# transformerless_power_Supply_5v.net
KiCad netlist of a schematic drawn in EAGLE
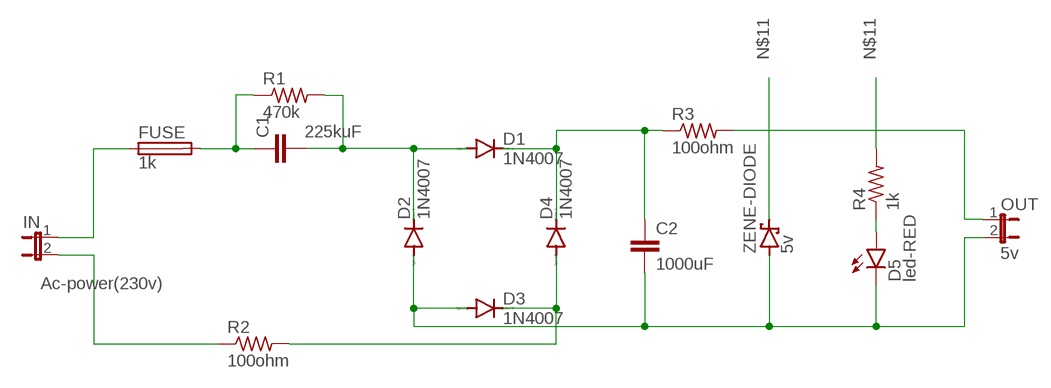
[diagram p0: schematic, sheet 1]

(export (version "E")
  (design (tool "Eeschema 10.0.6"))
  (components
    (comp (ref "C1")
      (value "225kuF")
      (footprint "eagle-import:C5B3")
      (libsource (lib "eagle-import") (part "C5/3"))
    )
    (comp (ref "C2")
      (value "1000uF")
      (footprint "eagle-import:C5B3")
      (libsource (lib "eagle-import") (part "C5/3"))
    )
    (comp (ref "D1")
      (value "1N4007")
      (footprint "eagle-import:DO41-10")
      (libsource (lib "eagle-import") (part "1N4004"))
    )
    (comp (ref "D2")
      (value "1N4007")
      (footprint "eagle-import:DO41-10")
      (libsource (lib "eagle-import") (part "1N4004"))
    )
    (comp (ref "D3")
      (value "1N4007")
      (footprint "eagle-import:DO41-10")
      (libsource (lib "eagle-import") (part "1N4004"))
    )
    (comp (ref "D4")
      (value "1N4007")
      (footprint "eagle-import:DO41-10")
      (libsource (lib "eagle-import") (part "1N4004"))
    )
    (comp (ref "D5")
      (value "led-RED")
      (footprint "eagle-import:SFH482")
      (libsource (lib "eagle-import") (part "SFH482"))
    )
    (comp (ref "FUSE")
      (value "1k")
      (footprint "eagle-import:PICOFUSE")
      (libsource (lib "eagle-import") (part "FUSEPICOFUSE"))
    )
    (comp (ref "IN")
      (value "Ac-power(230v)")
      (footprint "eagle-import:JP1")
      (libsource (lib "eagle-import") (part "JP1E"))
    )
    (comp (ref "OUT")
      (value "5v")
      (footprint "eagle-import:JP1")
      (libsource (lib "eagle-import") (part "JP1E"))
    )
    (comp (ref "R1")
      (value "470k")
      (footprint "eagle-import:0207_10")
      (libsource (lib "eagle-import") (part "R-US_0207/10"))
    )
    (comp (ref "R2")
      (value "100ohm")
      (footprint "eagle-import:0207_10")
      (libsource (lib "eagle-import") (part "R-US_0207/10"))
    )
    (comp (ref "R3")
      (value "100ohm")
      (footprint "eagle-import:0207_10")
      (libsource (lib "eagle-import") (part "R-US_0207/10"))
    )
    (comp (ref "R4")
      (value "1k")
      (footprint "eagle-import:0207_10")
      (libsource (lib "eagle-import") (part "R-US_0207/10"))
    )
    (comp (ref "ZENE-DIODE")
      (value "5v")
      (footprint "eagle-import:C1702-15")
      (libsource (lib "eagle-import") (part "P6KEXXA"))
    )
  )
  (nets
    (net (code "1") (name "/N$11") (class "Default")
      (node (ref "R4") (pin "2") (pinfunction "2_2") (pintype "passive"))
      (node (ref "ZENE-DIODE") (pin "C") (pinfunction "C_C") (pintype "passive"))
    )
    (net (code "2") (name "Net-(C1-Pad1)") (class "Default")
      (node (ref "C1") (pin "1") (pinfunction "1_1") (pintype "passive"))
      (node (ref "FUSE") (pin "2") (pinfunction "2_2") (pintype "passive"))
      (node (ref "R1") (pin "1") (pinfunction "1_1") (pintype "passive"))
    )
    (net (code "3") (name "Net-(C1-Pad2)") (class "Default")
      (node (ref "C1") (pin "2") (pinfunction "2_2") (pintype "passive"))
      (node (ref "D1") (pin "A") (pinfunction "A_A") (pintype "passive"))
      (node (ref "D2") (pin "C") (pinfunction "C_C") (pintype "passive"))
      (node (ref "R1") (pin "2") (pinfunction "2_2") (pintype "passive"))
    )
    (net (code "4") (name "Net-(C2-Pad1)") (class "Default")
      (node (ref "C2") (pin "1") (pinfunction "1_1") (pintype "passive"))
      (node (ref "D1") (pin "C") (pinfunction "C_C") (pintype "passive"))
      (node (ref "D4") (pin "C") (pinfunction "C_C") (pintype "passive"))
      (node (ref "R3") (pin "1") (pinfunction "1_1") (pintype "passive"))
    )
    (net (code "5") (name "Net-(D3-PadC)") (class "Default")
      (node (ref "D3") (pin "C") (pinfunction "C_C") (pintype "passive"))
      (node (ref "D4") (pin "A") (pinfunction "A_A") (pintype "passive"))
      (node (ref "R2") (pin "2") (pinfunction "2_2") (pintype "passive"))
    )
    (net (code "6") (name "Net-(D5-C)") (class "Default")
      (node (ref "C2") (pin "2") (pinfunction "2_2") (pintype "passive"))
      (node (ref "D2") (pin "A") (pinfunction "A_A") (pintype "passive"))
      (node (ref "D3") (pin "A") (pinfunction "A_A") (pintype "passive"))
      (node (ref "D5") (pin "K") (pinfunction "C_K") (pintype "passive"))
      (node (ref "OUT") (pin "2") (pinfunction "2_2") (pintype "passive"))
      (node (ref "ZENE-DIODE") (pin "A") (pinfunction "A_A") (pintype "passive"))
    )
    (net (code "7") (name "Net-(D5-PadA)") (class "Default")
      (node (ref "D5") (pin "A") (pinfunction "A_A") (pintype "passive"))
      (node (ref "R4") (pin "1") (pinfunction "1_1") (pintype "passive"))
    )
    (net (code "8") (name "Net-(FUSE-Pad1)") (class "Default")
      (node (ref "FUSE") (pin "1") (pinfunction "1_1") (pintype "passive"))
      (node (ref "IN") (pin "1") (pinfunction "1_1") (pintype "passive"))
    )
    (net (code "9") (name "Net-(IN-Pad2)") (class "Default")
      (node (ref "IN") (pin "2") (pinfunction "2_2") (pintype "passive"))
      (node (ref "R2") (pin "1") (pinfunction "1_1") (pintype "passive"))
    )
    (net (code "10") (name "Net-(OUT-Pad1)") (class "Default")
      (node (ref "OUT") (pin "1") (pinfunction "1_1") (pintype "passive"))
      (node (ref "R3") (pin "2") (pinfunction "2_2") (pintype "passive"))
    )
  )
)
